# Hedgehog.net
KiCad netlist of a schematic drawn in Altium Designer
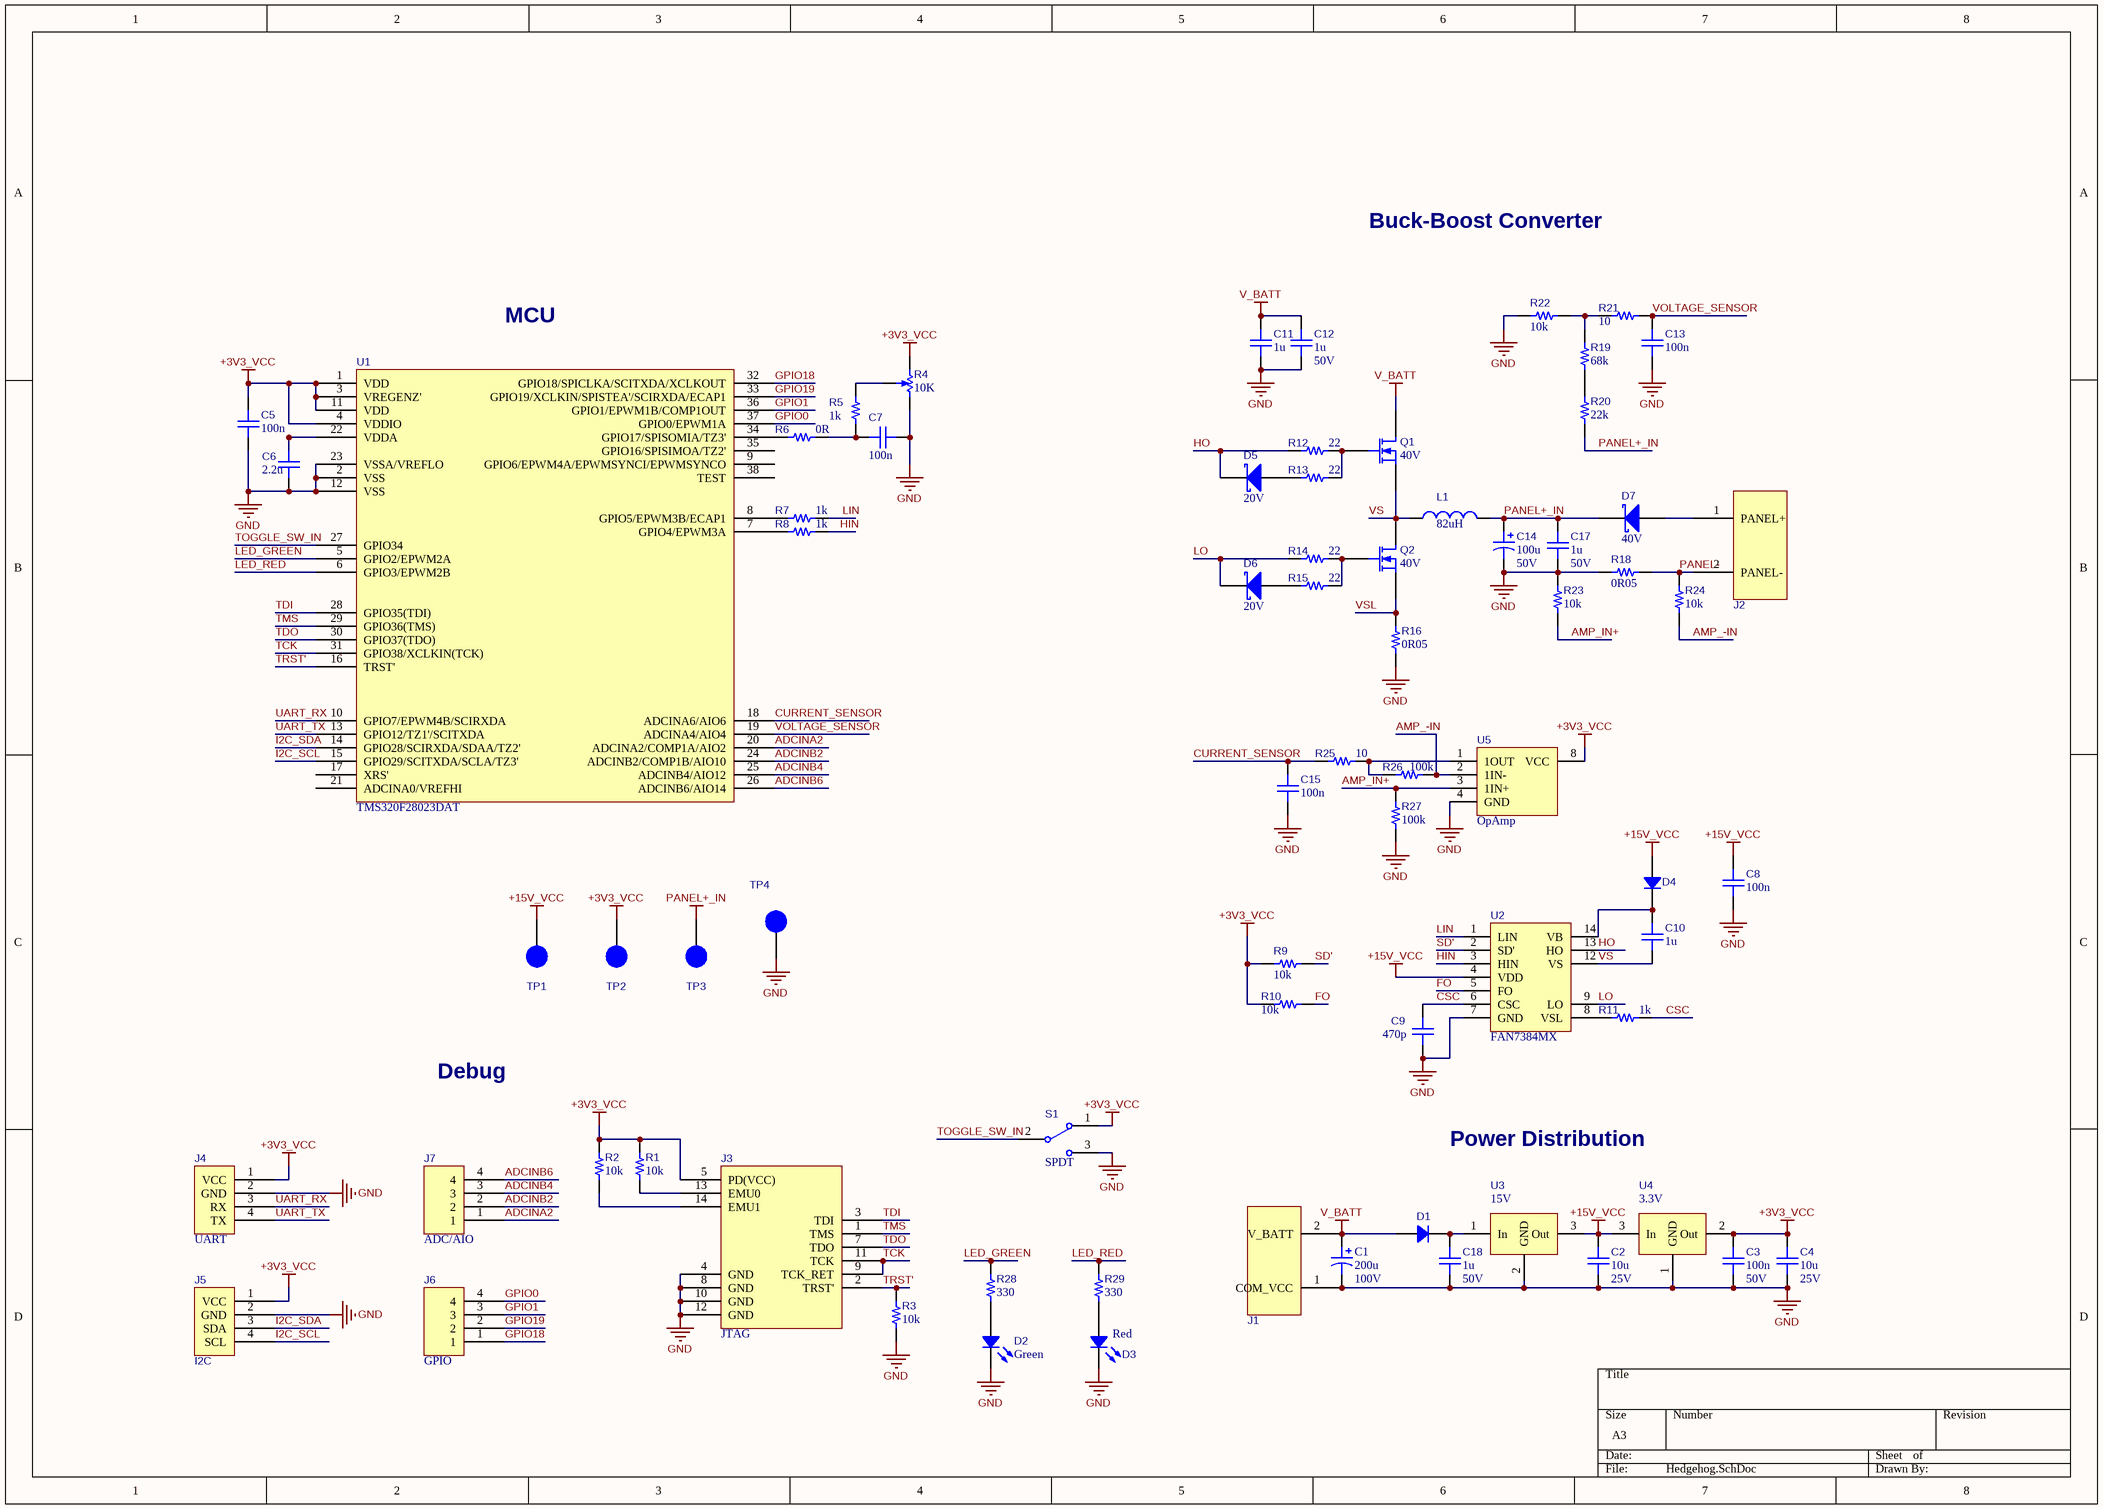
[diagram p0: Hedgehog.SchDoc]

(export (version "E")
  (design (tool "Eeschema 10.0.6"))
  (components
    (comp (ref "C1")
      (value "200u")
      (footprint "CAP-200uF-1000V-20%-THM-Radial")
      (description "Polarized Capacitor, 200uF, 100V Voltage Rating, Through Hole Radial Package")
      (fields (field (name "VOLTAGERATING") "100V"))
      (libsource (lib "hedgehog") (part "200u-100V-THM-Radial-20%"))
    )
    (comp (ref "C2")
      (value "10u")
      (footprint "CAP 1206/3216 Murata")
      (description "Capacitor, 10uF, 25V Voltage Rating, 1206 Package")
      (fields (field (name "VOLTAGERATING") "25V"))
      (libsource (lib "Capacitor SMD") (part "10u-25V-1206-10%"))
    )
    (comp (ref "C3")
      (value "100n")
      (footprint "CAP 0805/2012")
      (description "Capacitor, 100nF, 50V Voltage Rating, 0805 Package")
      (fields (field (name "VOLTAGERATING") "50V"))
      (libsource (lib "Capacitor SMD") (part "100n-50V-0805-10%"))
    )
    (comp (ref "C4")
      (value "10u")
      (footprint "CAP 1206/3216 Murata")
      (description "Capacitor, 10uF, 25V Voltage Rating, 1206 Package")
      (fields (field (name "VOLTAGERATING") "25V"))
      (libsource (lib "Capacitor SMD") (part "10u-25V-1206-10%"))
    )
    (comp (ref "C5")
      (value "100n")
      (footprint "CAP 0805/2012")
      (description "Capacitor, 100nF, 50V Voltage Rating, 0805 Package")
      (libsource (lib "Capacitor SMD") (part "100n-50V-0805-10%"))
    )
    (comp (ref "C6")
      (value "2.2u")
      (footprint "CAP 0805/2012")
      (description "Capacitor, 2.2uF, 25V Voltage Rating, 0805 Package")
      (libsource (lib "Capacitor SMD") (part "2.2u-25V-0805-10%"))
    )
    (comp (ref "C7")
      (value "100n")
      (footprint "CAP 0805/2012")
      (description "Capacitor, 100nF, 50V Voltage Rating, 0805 Package")
      (libsource (lib "Capacitor SMD") (part "100n-50V-0805-10%"))
    )
    (comp (ref "C8")
      (value "100n")
      (footprint "CAP 0805/2012")
      (description "Capacitor, 100nF, 50V Voltage Rating, 0805 Package")
      (libsource (lib "Capacitor SMD") (part "100n-50V-0805-10%"))
    )
    (comp (ref "C9")
      (value "470p")
      (footprint "CAP 0805/2012")
      (description "Capacitor, 470pF, 50V Voltage Rating, 0805 Package")
      (libsource (lib "Capacitor SMD") (part "470p-50V-0805-5%"))
    )
    (comp (ref "C10")
      (value "1u")
      (footprint "CAP 0805/2012")
      (description "Capacitor,1uF, 25V Voltage Rating, 0805 Package")
      (libsource (lib "Capacitor SMD") (part "1u-25V-0805-10%"))
    )
    (comp (ref "C11")
      (value "1u")
      (footprint "CAP-TH-Radial_1uF-Non_Polarised-KEMET")
      (description "Capacitor, 1uF, 63V Voltage Rating, RADIAL Package")
      (libsource (lib "PwrSupply-Schematics-Library") (part "1u-63V-THM-Radial-10%"))
    )
    (comp (ref "C12")
      (value "1u")
      (footprint "CAP 1206/3216 Murata")
      (description "Capacitor, 1uF, 50V Voltage Rating, 1206 Package")
      (fields (field (name "VOLTAGERATING") "50V"))
      (libsource (lib "Capacitor SMD") (part "1u-50V-1206-10%"))
    )
    (comp (ref "C13")
      (value "100n")
      (footprint "CAP 0805/2012")
      (description "Capacitor, 100nF, 50V Voltage Rating, 0805 Package")
      (libsource (lib "Capacitor SMD") (part "100n-50V-0805-10%"))
    )
    (comp (ref "C14")
      (value "100u")
      (footprint "CAP-100uF-50V-20%-THM-Radial Panasonic Electronic Components")
      (description "Polarized Capacitor, 100uF, 50V Voltage Rating, Through Hole Radial Package")
      (fields (field (name "VOLTAGERATING") "50V"))
      (libsource (lib "PwrSupply-Schematics-Library") (part "100u-50V-THM-Radial-20%"))
    )
    (comp (ref "C15")
      (value "100n")
      (footprint "CAP 0805/2012")
      (description "Capacitor, 100nF, 50V Voltage Rating, 0805 Package")
      (libsource (lib "Capacitor SMD") (part "100n-50V-0805-10%"))
    )
    (comp (ref "C17")
      (value "1u")
      (footprint "CAP 1206/3216 Murata")
      (description "Capacitor, 1uF, 50V Voltage Rating, 1206 Package")
      (fields (field (name "VOLTAGERATING") "50V"))
      (libsource (lib "Capacitor SMD") (part "1u-50V-1206-10%"))
    )
    (comp (ref "C18")
      (value "1u")
      (footprint "CAP 1206/3216 Murata")
      (description "Capacitor, 1uF, 50V Voltage Rating, 1206 Package")
      (fields (field (name "VOLTAGERATING") "50V"))
      (libsource (lib "Capacitor SMD") (part "1u-50V-1206-10%"))
    )
    (comp (ref "D1")
      (value "400V-1A-GenPurp-SMA")
      (footprint "SMA Diodes Incorporated")
      (description "Diode, 400V Voltage Rating, 1A Current Rating, General Purpose Type, SMA Package")
      (fields (field (name "MANUFACTURER") "ON Semiconductor"))
      (libsource (lib "Diode SMD") (part "400V-1A-GenPurp-SMA"))
    )
    (comp (ref "D2")
      (value "LED-Green-1206")
      (footprint "LED 1206/3216 Kingbright")
      (description "LED, Green Color, 1206 Package")
      (fields (field (name "MANUFACTURER") "Kingbright") (field (name "COLOR") "Green"))
      (libsource (lib "Diode SMD") (part "LED-Green-1206"))
    )
    (comp (ref "D3")
      (value "LED-Red-1206")
      (footprint "LED 1206/3216 Kingbright")
      (description "LED, Red Color, 1206 Package")
      (fields (field (name "MANUFACTURER") "Kingbright") (field (name "COLOR") "Red"))
      (libsource (lib "Diode SMD") (part "LED-Red-1206"))
    )
    (comp (ref "D4")
      (value "400V-2A-Fast-SMA")
      (footprint "SMA Diodes Incorporated")
      (description "Diode, 400V Voltage Rating, 2A Current Rating, Fast Type, SMA Package")
      (fields (field (name "MANUFACTURER") "ON Semiconductor"))
      (libsource (lib "Diode SMD") (part "400V-2A-Fast-SMA"))
    )
    (comp (ref "D5")
      (value "20V-1A-SCHOTTKY-SOD123W")
      (footprint "CFP3-SOD123W-Nexperia USA Inc.")
      (description "Diode, 20V Voltage Rating, 1A Current Rating, SCHOTTKY Type, SOD123W Package")
      (fields (field (name "MANUFACTURER") "Nexperia USA Inc.") (field (name "VOLTAGERATING") "20V"))
      (libsource (lib "PwrSupply-Schematics-Library") (part "20V-1A-SCHOTTKY-SOD123W"))
    )
    (comp (ref "D6")
      (value "20V-1A-SCHOTTKY-SOD123W")
      (footprint "CFP3-SOD123W-Nexperia USA Inc.")
      (description "Diode, 20V Voltage Rating, 1A Current Rating, SCHOTTKY Type, SOD123W Package")
      (fields (field (name "MANUFACTURER") "Nexperia USA Inc.") (field (name "VOLTAGERATING") "20V"))
      (libsource (lib "PwrSupply-Schematics-Library") (part "20V-1A-SCHOTTKY-SOD123W"))
    )
    (comp (ref "D7")
      (value "40V-5A-SCHOTTKY-SMC")
      (footprint "DIOM6959X25L")
      (description "Diode, 40V Voltage Rating, 5A Current Rating, SCHOTTKY Type, SMC Package")
      (fields (field (name "MANUFACTURER") "Diodes Incorporated") (field (name "VOLTAGERATING") "40V"))
      (libsource (lib "PwrSupply-Schematics-Library") (part "40V-5A-SCHOTTKY-SMC"))
    )
    (comp (ref "J1")
      (value "~")
      (footprint "TWO_PIN_CONNECTOR-15A-On Shore Technology Inc.")
      (description "Slide Toggle Switch, 300V Voltage Rating, 15A Current Rating,")
      (fields (field (name "MANUFACTURER") "On Shore Technology Inc."))
      (libsource (lib "") (part "TwoPin-Connector-15A-300V-THM_1"))
    )
    (comp (ref "J2")
      (value "~")
      (footprint "TWO_PIN_CONNECTOR-15A-On Shore Technology Inc.")
      (description "Slide Toggle Switch, 300V Voltage Rating, 15A Current Rating,")
      (fields (field (name "MANUFACTURER") "On Shore Technology Inc."))
      (libsource (lib "PwrSupply-Schematics-Library") (part "TwoPin-Connector-15A-300V-THM"))
    )
    (comp (ref "J3")
      (value "JTAG")
      (footprint "14Pin-Connector-2.54mmx2.54mmPitch On Shore Technology Inc.")
      (description "14Pin-Connector")
      (fields (field (name "MANUFACTURER") "On Shore Technology Inc."))
      (libsource (lib "PwrSupply-Schematics-Library") (part "14Pin-Connector"))
    )
    (comp (ref "J4")
      (value "UART")
      (footprint "4Pin_Connector-Wurth Electronics Inc.")
      (description "4Pin-Connector")
      (libsource (lib "PwrSupply-Schematics-Library") (part "4Pin-Connector"))
    )
    (comp (ref "J5")
      (value "I2C")
      (footprint "4Pin_Connector-Wurth Electronics Inc.")
      (description "4Pin-Connector")
      (libsource (lib "") (part "4Pin-Connector_2"))
    )
    (comp (ref "J6")
      (value "GPIO")
      (footprint "4Pin_Connector-Wurth Electronics Inc.")
      (description "4Pin-Connector")
      (libsource (lib "") (part "4Pin-Connector_1"))
    )
    (comp (ref "J7")
      (value "ADC/AIO")
      (footprint "4Pin_Connector-Wurth Electronics Inc.")
      (description "4Pin-Connector")
      (libsource (lib "") (part "4Pin-Connector_1"))
    )
    (comp (ref "L1")
      (value "82uH")
      (footprint "Inductor-82uH-Pulse Electronics Power")
      (description "82u, 6.5A Current Rating, 83mOhm Resistance, ThroughHole Package")
      (libsource (lib "PwrSupply-Schematics-Library") (part "82uH-6.5A-83mOhm"))
    )
    (comp (ref "Q1")
      (value "40V")
      (footprint "DPAK/TO252-3-5.46mmWidth(Tab) ON Semiconductor - VIAS")
      (description "N-CH, 40V Voltage Rating, 6A Current Rating,  1.71W Power Rating, DPAK Package")
      (libsource (lib "PwrSupply-Schematics-Library") (part "Mosfet-40V-6A-1.71W-SMD-DPAK"))
    )
    (comp (ref "Q2")
      (value "40V")
      (footprint "DPAK/TO252-3-5.46mmWidth(Tab) ON Semiconductor - VIAS")
      (description "N-CH, 40V Voltage Rating, 6A Current Rating,  1.71W Power Rating, DPAK Package")
      (libsource (lib "PwrSupply-Schematics-Library") (part "Mosfet-40V-6A-1.71W-SMD-DPAK"))
    )
    (comp (ref "R1")
      (value "10k")
      (footprint "RES 0805/2012")
      (description "Resistor, 10k, 125mW Power Rating, 0805 Package")
      (libsource (lib "Resistor SMD") (part "10k-125mW-0805-1%"))
    )
    (comp (ref "R2")
      (value "10k")
      (footprint "RES 0805/2012")
      (description "Resistor, 10k, 125mW Power Rating, 0805 Package")
      (libsource (lib "Resistor SMD") (part "10k-125mW-0805-1%"))
    )
    (comp (ref "R3")
      (value "10k")
      (footprint "RES 0805/2012")
      (description "Resistor, 10k, 125mW Power Rating, 0805 Package")
      (libsource (lib "Resistor SMD") (part "10k-125mW-0805-1%"))
    )
    (comp (ref "R4")
      (value "10K")
      (footprint "Potentiometer-TC33X-2-103E-Bourns Inc.")
      (description "Potentiometer, 10kOhm Resistance, Current Rating, 0.1W Power Rating")
      (fields (field (name "MANUFACTURER") "Bourns Inc."))
      (libsource (lib "PwrSupply-Schematics-Library") (part "Pot-10kOhm-0.1W-20%"))
    )
    (comp (ref "R5")
      (value "1k")
      (footprint "RES 0805/2012")
      (description "Resistor, 1k, 125mW Power Rating, 0805 Package")
      (libsource (lib "Resistor SMD") (part "1k-125mW-0805-1%"))
    )
    (comp (ref "R6")
      (value "0R")
      (footprint "RES 0805/2012")
      (description "Resistor, 0 , 125mW Power Rating, 0805 Package")
      (libsource (lib "Resistor SMD") (part "0k-125mW-0805-Jumper"))
    )
    (comp (ref "R7")
      (value "1k")
      (footprint "RES 0805/2012")
      (description "Resistor, 1k, 125mW Power Rating, 0805 Package")
      (libsource (lib "Resistor SMD") (part "1k-125mW-0805-1%"))
    )
    (comp (ref "R8")
      (value "1k")
      (footprint "RES 0805/2012")
      (description "Resistor, 1k, 125mW Power Rating, 0805 Package")
      (libsource (lib "Resistor SMD") (part "1k-125mW-0805-1%"))
    )
    (comp (ref "R9")
      (value "10k")
      (footprint "RES 0805/2012")
      (description "Resistor, 10k, 125mW Power Rating, 0805 Package")
      (libsource (lib "Resistor SMD") (part "10k-125mW-0805-1%"))
    )
    (comp (ref "R10")
      (value "10k")
      (footprint "RES 0805/2012")
      (description "Resistor, 10k, 125mW Power Rating, 0805 Package")
      (libsource (lib "Resistor SMD") (part "10k-125mW-0805-1%"))
    )
    (comp (ref "R11")
      (value "1k")
      (footprint "RES 0805/2012")
      (description "Resistor, 1k, 125mW Power Rating, 0805 Package")
      (libsource (lib "Resistor SMD") (part "1k-125mW-0805-1%"))
    )
    (comp (ref "R12")
      (value "22")
      (footprint "RES 0805/2012")
      (description "Resistor, 22, 125mW Power Rating, 0805 Package")
      (libsource (lib "Resistor SMD") (part "22-125mW-0805-1%"))
    )
    (comp (ref "R13")
      (value "22")
      (footprint "RES 0805/2012")
      (description "Resistor, 22, 125mW Power Rating, 0805 Package")
      (libsource (lib "Resistor SMD") (part "22-125mW-0805-1%"))
    )
    (comp (ref "R14")
      (value "22")
      (footprint "RES 0805/2012")
      (description "Resistor, 22, 125mW Power Rating, 0805 Package")
      (libsource (lib "Resistor SMD") (part "22-125mW-0805-1%"))
    )
    (comp (ref "R15")
      (value "22")
      (footprint "RES 0805/2012")
      (description "Resistor, 22, 125mW Power Rating, 0805 Package")
      (libsource (lib "Resistor SMD") (part "22-125mW-0805-1%"))
    )
    (comp (ref "R16")
      (value "0R05")
      (footprint "RES 2512/6432")
      (description "Resistor, 0.05 Ohm, 3W Power Rating, 2512 Package")
      (libsource (lib "PwrSupply-Schematics-Library") (part "RES-0.05-3W-SMD-2512-1%"))
    )
    (comp (ref "R18")
      (value "0R05")
      (footprint "RES 2512/6432")
      (description "Resistor, 0.05 Ohm, 3W Power Rating, 2512 Package")
      (libsource (lib "PwrSupply-Schematics-Library") (part "RES-0.05-3W-SMD-2512-1%"))
    )
    (comp (ref "R19")
      (value "68k")
      (footprint "RES 0805/2012")
      (description "Resistor, 68k, 125mW Power Rating, Package")
      (libsource (lib "Resistor SMD") (part "68k-125mW-0805-1%"))
    )
    (comp (ref "R20")
      (value "22k")
      (footprint "RES 0805/2012")
      (description "Resistor, 22k, 125mW Power Rating, 0805 Package")
      (libsource (lib "Resistor SMD") (part "22k-125mW-0805-1%"))
    )
    (comp (ref "R21")
      (value "10")
      (footprint "RES 0805/2012")
      (description "Resistor, 10, 125mW Power Rating, 0805 Package")
      (libsource (lib "Resistor SMD") (part "10-125mW-0805-1%"))
    )
    (comp (ref "R22")
      (value "10k")
      (footprint "RES 0805/2012")
      (description "Resistor, 10k, 125mW Power Rating, 0805 Package")
      (libsource (lib "Resistor SMD") (part "10k-125mW-0805-1%"))
    )
    (comp (ref "R23")
      (value "10k")
      (footprint "RES 0805/2012")
      (description "Resistor, 10k, 125mW Power Rating, 0805 Package")
      (libsource (lib "Resistor SMD") (part "10k-125mW-0805-1%"))
    )
    (comp (ref "R24")
      (value "10k")
      (footprint "RES 0805/2012")
      (description "Resistor, 10k, 125mW Power Rating, 0805 Package")
      (libsource (lib "Resistor SMD") (part "10k-125mW-0805-1%"))
    )
    (comp (ref "R25")
      (value "10")
      (footprint "RES 0805/2012")
      (description "Resistor, 10, 125mW Power Rating, 0805 Package")
      (libsource (lib "Resistor SMD") (part "10-125mW-0805-1%"))
    )
    (comp (ref "R26")
      (value "100k")
      (footprint "RES 0805/2012")
      (description "Resistor, 100k, 125mW Power Rating, 0805 Package")
      (libsource (lib "Resistor SMD") (part "100k-125mW-0805-1%"))
    )
    (comp (ref "R27")
      (value "100k")
      (footprint "RES 0805/2012")
      (description "Resistor, 100k, 125mW Power Rating, 0805 Package")
      (libsource (lib "Resistor SMD") (part "100k-125mW-0805-1%"))
    )
    (comp (ref "R28")
      (value "330")
      (footprint "RES 0805/2012")
      (description "Resistor, 330, 125mW Power Rating, 0805 Package")
      (libsource (lib "Resistor SMD") (part "330-125mW-0805-1%"))
    )
    (comp (ref "R29")
      (value "330")
      (footprint "RES 0805/2012")
      (description "Resistor, 330, 125mW Power Rating, 0805 Package")
      (libsource (lib "Resistor SMD") (part "330-125mW-0805-1%"))
    )
    (comp (ref "S1")
      (value "SPDT")
      (footprint "Toggle_Switch-SPDT-C&K")
      (description "Slide Toggle Switch, 12V Voltage Rating, 100mA Current Rating, Through Hole Package")
      (fields (field (name "MANUFACTURER") "C&K"))
      (libsource (lib "PwrSupply-Schematics-Library") (part "ToggleSwitch-SPDT-12V-100mA"))
    )
    (comp (ref "TP1")
      (value "TP_2mm_round")
      (footprint "TP_2mm_round")
      (libsource (lib "hedgehog") (part "TP_2mm_round"))
    )
    (comp (ref "TP2")
      (value "TP_2mm_round")
      (footprint "TP_2mm_round")
      (libsource (lib "hedgehog") (part "TP_2mm_round"))
    )
    (comp (ref "TP3")
      (value "TP_2mm_round")
      (footprint "TP_2mm_round")
      (libsource (lib "hedgehog") (part "TP_2mm_round"))
    )
    (comp (ref "TP4")
      (value "TP_2mm_round")
      (footprint "TP_2mm_round")
      (libsource (lib "hedgehog") (part "TP_2mm_round"))
    )
    (comp (ref "U1")
      (value "TMS320F28023DAT")
      (description "IC MCU 32BIT 64KB FLASH 38TSSOP")
      (fields (field (name "MANUFACTURER") "Texas Instruments"))
      (libsource (lib "PwrSupply-Schematics-Library") (part "MC-TMS320F28023DAT_Modified"))
    )
    (comp (ref "U2")
      (value "FAN7384MX")
      (footprint "14SOIC-3.9mmWidth ON Semiconductor")
      (description "Half-Bridge Gate Driver IC Non-Inverting 14-SOIC")
      (fields (field (name "MANUFACTURER") "ON Semiconductor"))
      (libsource (lib "IC Driver") (part "FAN7384MX"))
    )
    (comp (ref "U3")
      (value "15V")
      (footprint "DPAK/TO252-3-5.46mmWidth(Tab) ON Semiconductor")
      (description "Voltage Regulator, 15V OutputVoltage, 1A MaxCurrent, LDO Type, DPAK Package")
      (fields (field (name "MANUFACTURER") "ON Semiconductor") (field (name "OUTPUTVOLTAGE") "15V"))
      (libsource (lib "PwrSupply-Schematics-Library") (part "15V-1A-LDO-SMD-DPAK"))
    )
    (comp (ref "U4")
      (value "Voltage Regulator")
      (footprint "SOT223/TO261-4 Diodes Incorporated")
      (description "Voltage Regulator, 3.3V OutputVoltage, 1A MaxCurrent, LDO Type, SOT223 Package")
      (fields (field (name "MANUFACTURER") "Diodes Incorporated") (field (name "OUTPUTVOLTAGE") "3.3V"))
      (libsource (lib "IC Regulator") (part "3.3V-1A-LDO-SMD-SOT223_2"))
    )
    (comp (ref "U5")
      (value "OpAmp")
      (footprint "8SOIC-3.9mmWidth")
      (description "IC OPAMP GP 700KHZ 8SOIC")
      (fields (field (name "MANUFACTURER") "Texas Instruments"))
      (libsource (lib "IC OpAmp") (part "LM358AD"))
    )
  )
  (nets
    (net (code "1") (name "+3V3_VCC") (class "Default")
      (node (ref "C3") (pin "2") (pinfunction "2_2") (pintype "passive"))
      (node (ref "C4") (pin "1") (pinfunction "1_1") (pintype "passive"))
      (node (ref "C5") (pin "2") (pinfunction "2_2") (pintype "passive"))
      (node (ref "J3") (pin "5") (pinfunction "PD(VCC)_5") (pintype "passive"))
      (node (ref "J4") (pin "1") (pinfunction "VCC_1") (pintype "passive"))
      (node (ref "J5") (pin "1") (pinfunction "VCC_1") (pintype "passive"))
      (node (ref "R1") (pin "2") (pinfunction "2_2") (pintype "passive"))
      (node (ref "R10") (pin "1") (pinfunction "1_1") (pintype "passive"))
      (node (ref "R2") (pin "2") (pinfunction "2_2") (pintype "passive"))
      (node (ref "R4") (pin "3") (pinfunction "CW_3") (pintype "passive"))
      (node (ref "R9") (pin "1") (pinfunction "1_1") (pintype "passive"))
      (node (ref "S1") (pin "1") (pinfunction "3_1") (pintype "passive"))
      (node (ref "TP2") (pin "0") (pinfunction "0_0") (pintype "passive"))
      (node (ref "U1") (pin "1") (pinfunction "VDD_1") (pintype "passive"))
      (node (ref "U1") (pin "11") (pinfunction "VDD_11") (pintype "passive"))
      (node (ref "U1") (pin "3") (pinfunction "VREGENZ'_3") (pintype "passive"))
      (node (ref "U1") (pin "4") (pinfunction "VDDIO_4") (pintype "passive"))
      (node (ref "U4") (pin "2") (pinfunction "Out_2") (pintype "passive"))
      (node (ref "U5") (pin "8") (pinfunction "VCC_8") (pintype "passive"))
    )
    (net (code "2") (name "+15V_VCC") (class "Default")
      (node (ref "C2") (pin "1") (pinfunction "1_1") (pintype "passive"))
      (node (ref "C8") (pin "1") (pinfunction "1_1") (pintype "passive"))
      (node (ref "D4") (pin "1") (pinfunction "1_1") (pintype "passive"))
      (node (ref "TP1") (pin "0") (pinfunction "0_0") (pintype "passive"))
      (node (ref "U2") (pin "4") (pinfunction "VDD_4") (pintype "passive"))
      (node (ref "U3") (pin "3") (pinfunction "Out_3") (pintype "passive"))
      (node (ref "U4") (pin "3") (pinfunction "In_3") (pintype "passive"))
    )
    (net (code "3") (name "/ADCINA2") (class "Default")
      (node (ref "J7") (pin "1") (pinfunction "1_1") (pintype "passive"))
      (node (ref "U1") (pin "20") (pinfunction "ADCINA2/COMP1A/AIO2_20") (pintype "passive"))
    )
    (net (code "4") (name "/ADCINB2") (class "Default")
      (node (ref "J7") (pin "2") (pinfunction "2_2") (pintype "passive"))
      (node (ref "U1") (pin "24") (pinfunction "ADCINB2/COMP1B/AIO10_24") (pintype "passive"))
    )
    (net (code "5") (name "/ADCINB4") (class "Default")
      (node (ref "J7") (pin "3") (pinfunction "3_3") (pintype "passive"))
      (node (ref "U1") (pin "25") (pinfunction "ADCINB4/AIO12_25") (pintype "passive"))
    )
    (net (code "6") (name "/ADCINB6") (class "Default")
      (node (ref "J7") (pin "4") (pinfunction "4_4") (pintype "passive"))
      (node (ref "U1") (pin "26") (pinfunction "ADCINB6/AIO14_26") (pintype "passive"))
    )
    (net (code "7") (name "/AMP_-IN") (class "Default")
      (node (ref "R24") (pin "1") (pinfunction "1_1") (pintype "passive"))
      (node (ref "R26") (pin "2") (pinfunction "2_2") (pintype "passive"))
      (node (ref "U5") (pin "2") (pinfunction "1IN-_2") (pintype "passive"))
    )
    (net (code "8") (name "/AMP_IN+") (class "Default")
      (node (ref "R23") (pin "1") (pinfunction "1_1") (pintype "passive"))
      (node (ref "R27") (pin "1") (pinfunction "1_1") (pintype "passive"))
      (node (ref "U5") (pin "3") (pinfunction "1IN+_3") (pintype "passive"))
    )
    (net (code "9") (name "/CSC") (class "Default")
      (node (ref "C9") (pin "2") (pinfunction "2_2") (pintype "passive"))
      (node (ref "R11") (pin "1") (pinfunction "1_1") (pintype "passive"))
      (node (ref "U2") (pin "6") (pinfunction "CSC_6") (pintype "passive"))
    )
    (net (code "10") (name "/CURRENT_SENSOR") (class "Default")
      (node (ref "C15") (pin "1") (pinfunction "1_1") (pintype "passive"))
      (node (ref "R25") (pin "2") (pinfunction "2_2") (pintype "passive"))
      (node (ref "U1") (pin "18") (pinfunction "ADCINA6/AIO6_18") (pintype "passive"))
    )
    (net (code "11") (name "/FO") (class "Default")
      (node (ref "R10") (pin "2") (pinfunction "2_2") (pintype "passive"))
      (node (ref "U2") (pin "5") (pinfunction "FO_5") (pintype "passive"))
    )
    (net (code "12") (name "/GPIO0") (class "Default")
      (node (ref "J6") (pin "4") (pinfunction "4_4") (pintype "passive"))
      (node (ref "U1") (pin "37") (pinfunction "GPIO0/EPWM1A_37") (pintype "passive"))
    )
    (net (code "13") (name "/GPIO1") (class "Default")
      (node (ref "J6") (pin "3") (pinfunction "3_3") (pintype "passive"))
      (node (ref "U1") (pin "36") (pinfunction "GPIO1/EPWM1B/COMP1OUT_36") (pintype "passive"))
    )
    (net (code "14") (name "/GPIO18") (class "Default")
      (node (ref "J6") (pin "1") (pinfunction "1_1") (pintype "passive"))
      (node (ref "U1") (pin "32") (pinfunction "GPIO18/SPICLKA/SCITXDA/XCLKOUT_32") (pintype "passive"))
    )
    (net (code "15") (name "/GPIO19") (class "Default")
      (node (ref "J6") (pin "2") (pinfunction "2_2") (pintype "passive"))
      (node (ref "U1") (pin "33") (pinfunction "GPIO19/XCLKIN/SPISTEA'/SCIRXDA/ECAP1_33") (pintype "passive"))
    )
    (net (code "16") (name "/HIN") (class "Default")
      (node (ref "R8") (pin "2") (pinfunction "2_2") (pintype "passive"))
      (node (ref "U2") (pin "3") (pinfunction "HIN_3") (pintype "passive"))
    )
    (net (code "17") (name "/HO") (class "Default")
      (node (ref "D5") (pin "2") (pinfunction "K_2") (pintype "passive"))
      (node (ref "R12") (pin "1") (pinfunction "1_1") (pintype "passive"))
      (node (ref "U2") (pin "13") (pinfunction "HO_13") (pintype "passive"))
    )
    (net (code "18") (name "/I2C_SCL") (class "Default")
      (node (ref "J5") (pin "4") (pinfunction "SCL_4") (pintype "passive"))
      (node (ref "U1") (pin "15") (pinfunction "GPIO29/SCITXDA/SCLA/TZ3'_15") (pintype "passive"))
    )
    (net (code "19") (name "/I2C_SDA") (class "Default")
      (node (ref "J5") (pin "3") (pinfunction "SDA_3") (pintype "passive"))
      (node (ref "U1") (pin "14") (pinfunction "GPIO28/SCIRXDA/SDAA/TZ2'_14") (pintype "passive"))
    )
    (net (code "20") (name "/LED_GREEN") (class "Default")
      (node (ref "R28") (pin "2") (pinfunction "2_2") (pintype "passive"))
      (node (ref "U1") (pin "5") (pinfunction "GPIO2/EPWM2A_5") (pintype "passive"))
    )
    (net (code "21") (name "/LED_RED") (class "Default")
      (node (ref "R29") (pin "2") (pinfunction "2_2") (pintype "passive"))
      (node (ref "U1") (pin "6") (pinfunction "GPIO3/EPWM2B_6") (pintype "passive"))
    )
    (net (code "22") (name "/LIN") (class "Default")
      (node (ref "R7") (pin "2") (pinfunction "2_2") (pintype "passive"))
      (node (ref "U2") (pin "1") (pinfunction "LIN_1") (pintype "passive"))
    )
    (net (code "23") (name "/LO") (class "Default")
      (node (ref "D6") (pin "2") (pinfunction "K_2") (pintype "passive"))
      (node (ref "R14") (pin "1") (pinfunction "1_1") (pintype "passive"))
      (node (ref "U2") (pin "9") (pinfunction "LO_9") (pintype "passive"))
    )
    (net (code "24") (name "/PANEL-") (class "Default")
      (node (ref "J2") (pin "2") (pinfunction "PANEL-_2") (pintype "passive"))
      (node (ref "R18") (pin "2") (pinfunction "2_2") (pintype "passive"))
      (node (ref "R24") (pin "2") (pinfunction "2_2") (pintype "passive"))
    )
    (net (code "25") (name "/SD'") (class "Default")
      (node (ref "R9") (pin "2") (pinfunction "2_2") (pintype "passive"))
      (node (ref "U2") (pin "2") (pinfunction "SD'_2") (pintype "passive"))
    )
    (net (code "26") (name "/TCK") (class "Default")
      (node (ref "J3") (pin "11") (pinfunction "TCK_11") (pintype "passive"))
      (node (ref "J3") (pin "9") (pinfunction "TCK_RET_9") (pintype "passive"))
      (node (ref "U1") (pin "31") (pinfunction "GPIO38/XCLKIN(TCK)_31") (pintype "passive"))
    )
    (net (code "27") (name "/TDI") (class "Default")
      (node (ref "J3") (pin "3") (pinfunction "TDI_3") (pintype "passive"))
      (node (ref "U1") (pin "28") (pinfunction "GPIO35(TDI)_28") (pintype "passive"))
    )
    (net (code "28") (name "/TDO") (class "Default")
      (node (ref "J3") (pin "7") (pinfunction "TDO_7") (pintype "passive"))
      (node (ref "U1") (pin "30") (pinfunction "GPIO37(TDO)_30") (pintype "passive"))
    )
    (net (code "29") (name "/TMS") (class "Default")
      (node (ref "J3") (pin "1") (pinfunction "TMS_1") (pintype "passive"))
      (node (ref "U1") (pin "29") (pinfunction "GPIO36(TMS)_29") (pintype "passive"))
    )
    (net (code "30") (name "/TOGGLE_SW_IN") (class "Default")
      (node (ref "S1") (pin "2") (pinfunction "2_2") (pintype "passive"))
      (node (ref "U1") (pin "27") (pinfunction "GPIO34_27") (pintype "passive"))
    )
    (net (code "31") (name "/TRST'") (class "Default")
      (node (ref "J3") (pin "2") (pinfunction "TRST'_2") (pintype "passive"))
      (node (ref "R3") (pin "2") (pinfunction "2_2") (pintype "passive"))
      (node (ref "U1") (pin "16") (pinfunction "TRST'_16") (pintype "passive"))
    )
    (net (code "32") (name "/UART_RX") (class "Default")
      (node (ref "J4") (pin "3") (pinfunction "RX_3") (pintype "passive"))
      (node (ref "U1") (pin "10") (pinfunction "GPIO7/EPWM4B/SCIRXDA_10") (pintype "passive"))
    )
    (net (code "33") (name "/UART_TX") (class "Default")
      (node (ref "J4") (pin "4") (pinfunction "TX_4") (pintype "passive"))
      (node (ref "U1") (pin "13") (pinfunction "GPIO12/TZ1'/SCITXDA_13") (pintype "passive"))
    )
    (net (code "34") (name "/VOLTAGE_SENSOR") (class "Default")
      (node (ref "C13") (pin "2") (pinfunction "2_2") (pintype "passive"))
      (node (ref "R21") (pin "2") (pinfunction "2_2") (pintype "passive"))
      (node (ref "U1") (pin "19") (pinfunction "ADCINA4/AIO4_19") (pintype "passive"))
    )
    (net (code "35") (name "/VS") (class "Default")
      (node (ref "C10") (pin "1") (pinfunction "1_1") (pintype "passive"))
      (node (ref "L1") (pin "1") (pinfunction "1_1") (pintype "passive"))
      (node (ref "Q1") (pin "3") (pinfunction "S_3") (pintype "passive"))
      (node (ref "Q2") (pin "2") (pinfunction "D_2") (pintype "passive"))
      (node (ref "U2") (pin "12") (pinfunction "VS_12") (pintype "passive"))
    )
    (net (code "36") (name "/VSL") (class "Default")
      (node (ref "Q2") (pin "3") (pinfunction "S_3") (pintype "passive"))
      (node (ref "R16") (pin "2") (pinfunction "2_2") (pintype "passive"))
    )
    (net (code "37") (name "GND") (class "Default")
      (node (ref "C1") (pin "2") (pinfunction "2_2") (pintype "passive"))
      (node (ref "C11") (pin "1") (pinfunction "1_1") (pintype "passive"))
      (node (ref "C12") (pin "1") (pinfunction "1_1") (pintype "passive"))
      (node (ref "C13") (pin "1") (pinfunction "1_1") (pintype "passive"))
      (node (ref "C14") (pin "2") (pinfunction "2_2") (pintype "passive"))
      (node (ref "C15") (pin "2") (pinfunction "2_2") (pintype "passive"))
      (node (ref "C17") (pin "1") (pinfunction "1_1") (pintype "passive"))
      (node (ref "C18") (pin "1") (pinfunction "1_1") (pintype "passive"))
      (node (ref "C2") (pin "2") (pinfunction "2_2") (pintype "passive"))
      (node (ref "C3") (pin "1") (pinfunction "1_1") (pintype "passive"))
      (node (ref "C4") (pin "2") (pinfunction "2_2") (pintype "passive"))
      (node (ref "C5") (pin "1") (pinfunction "1_1") (pintype "passive"))
      (node (ref "C6") (pin "1") (pinfunction "1_1") (pintype "passive"))
      (node (ref "C7") (pin "1") (pinfunction "1_1") (pintype "passive"))
      (node (ref "C8") (pin "2") (pinfunction "2_2") (pintype "passive"))
      (node (ref "C9") (pin "1") (pinfunction "1_1") (pintype "passive"))
      (node (ref "D2") (pin "2") (pinfunction "2_2") (pintype "passive"))
      (node (ref "D3") (pin "2") (pinfunction "2_2") (pintype "passive"))
      (node (ref "J1") (pin "1") (pinfunction "COM_VCC_1") (pintype "passive"))
      (node (ref "J3") (pin "10") (pinfunction "GND_10") (pintype "passive"))
      (node (ref "J3") (pin "12") (pinfunction "GND_12") (pintype "passive"))
      (node (ref "J3") (pin "4") (pinfunction "GND_4") (pintype "passive"))
      (node (ref "J3") (pin "8") (pinfunction "GND_8") (pintype "passive"))
      (node (ref "J4") (pin "2") (pinfunction "GND_2") (pintype "passive"))
      (node (ref "J5") (pin "2") (pinfunction "GND_2") (pintype "passive"))
      (node (ref "R16") (pin "1") (pinfunction "1_1") (pintype "passive"))
      (node (ref "R18") (pin "1") (pinfunction "1_1") (pintype "passive"))
      (node (ref "R22") (pin "2") (pinfunction "2_2") (pintype "passive"))
      (node (ref "R23") (pin "2") (pinfunction "2_2") (pintype "passive"))
      (node (ref "R27") (pin "2") (pinfunction "2_2") (pintype "passive"))
      (node (ref "R3") (pin "1") (pinfunction "1_1") (pintype "passive"))
      (node (ref "R4") (pin "1") (pinfunction "CCW_1") (pintype "passive"))
      (node (ref "S1") (pin "3") (pinfunction "1_3") (pintype "passive"))
      (node (ref "TP4") (pin "0") (pinfunction "0_0") (pintype "passive"))
      (node (ref "U1") (pin "12") (pinfunction "VSS_12") (pintype "passive"))
      (node (ref "U1") (pin "2") (pinfunction "VSS_2") (pintype "passive"))
      (node (ref "U1") (pin "23") (pinfunction "VSSA/VREFLO_23") (pintype "passive"))
      (node (ref "U2") (pin "7") (pinfunction "GND_7") (pintype "passive"))
      (node (ref "U3") (pin "2") (pinfunction "GND_2") (pintype "passive"))
      (node (ref "U4") (pin "1") (pinfunction "GND_1") (pintype "passive"))
      (node (ref "U5") (pin "4") (pinfunction "GND_4") (pintype "passive"))
    )
    (net (code "38") (name "Net-(C7-Pad2)") (class "Default")
      (node (ref "C7") (pin "2") (pinfunction "2_2") (pintype "passive"))
      (node (ref "R5") (pin "1") (pinfunction "1_1") (pintype "passive"))
      (node (ref "R6") (pin "2") (pinfunction "2_2") (pintype "passive"))
    )
    (net (code "39") (name "Net-(D2-Pad1)") (class "Default")
      (node (ref "D2") (pin "1") (pinfunction "1_1") (pintype "passive"))
      (node (ref "R28") (pin "1") (pinfunction "1_1") (pintype "passive"))
    )
    (net (code "40") (name "Net-(D3-Pad1)") (class "Default")
      (node (ref "D3") (pin "1") (pinfunction "1_1") (pintype "passive"))
      (node (ref "R29") (pin "1") (pinfunction "1_1") (pintype "passive"))
    )
    (net (code "41") (name "Net-(D5-A)") (class "Default")
      (node (ref "D5") (pin "1") (pinfunction "A_1") (pintype "passive"))
      (node (ref "R13") (pin "1") (pinfunction "1_1") (pintype "passive"))
    )
    (net (code "42") (name "Net-(D6-A)") (class "Default")
      (node (ref "D6") (pin "1") (pinfunction "A_1") (pintype "passive"))
      (node (ref "R15") (pin "1") (pinfunction "1_1") (pintype "passive"))
    )
    (net (code "43") (name "Net-(D7-A)") (class "Default")
      (node (ref "D7") (pin "1") (pinfunction "A_1") (pintype "passive"))
      (node (ref "J2") (pin "1") (pinfunction "PANEL+_1") (pintype "passive"))
    )
    (net (code "44") (name "Net-(J3-EMU0)") (class "Default")
      (node (ref "J3") (pin "13") (pinfunction "EMU0_13") (pintype "passive"))
      (node (ref "R1") (pin "1") (pinfunction "1_1") (pintype "passive"))
    )
    (net (code "45") (name "Net-(J3-EMU1)") (class "Default")
      (node (ref "J3") (pin "14") (pinfunction "EMU1_14") (pintype "passive"))
      (node (ref "R2") (pin "1") (pinfunction "1_1") (pintype "passive"))
    )
    (net (code "46") (name "Net-(Q1-G)") (class "Default")
      (node (ref "Q1") (pin "1") (pinfunction "G_1") (pintype "passive"))
      (node (ref "R12") (pin "2") (pinfunction "2_2") (pintype "passive"))
      (node (ref "R13") (pin "2") (pinfunction "2_2") (pintype "passive"))
    )
    (net (code "47") (name "Net-(Q2-G)") (class "Default")
      (node (ref "Q2") (pin "1") (pinfunction "G_1") (pintype "passive"))
      (node (ref "R14") (pin "2") (pinfunction "2_2") (pintype "passive"))
      (node (ref "R15") (pin "2") (pinfunction "2_2") (pintype "passive"))
    )
    (net (code "48") (name "Net-(R4-W)") (class "Default")
      (node (ref "R4") (pin "2") (pinfunction "W_2") (pintype "passive"))
      (node (ref "R5") (pin "2") (pinfunction "2_2") (pintype "passive"))
    )
    (net (code "49") (name "Net-(R19-Pad1)") (class "Default")
      (node (ref "R19") (pin "1") (pinfunction "1_1") (pintype "passive"))
      (node (ref "R20") (pin "2") (pinfunction "2_2") (pintype "passive"))
    )
    (net (code "50") (name "Net-(R19-Pad2)") (class "Default")
      (node (ref "R19") (pin "2") (pinfunction "2_2") (pintype "passive"))
      (node (ref "R21") (pin "1") (pinfunction "1_1") (pintype "passive"))
      (node (ref "R22") (pin "1") (pinfunction "1_1") (pintype "passive"))
    )
    (net (code "51") (name "Net-(U1-GPIO4{slash}EPWM3A)") (class "Default")
      (node (ref "R8") (pin "1") (pinfunction "1_1") (pintype "passive"))
      (node (ref "U1") (pin "7") (pinfunction "GPIO4/EPWM3A_7") (pintype "passive"))
    )
    (net (code "52") (name "Net-(U1-GPIO5{slash}EPWM3B{slash}ECAP1)") (class "Default")
      (node (ref "R7") (pin "1") (pinfunction "1_1") (pintype "passive"))
      (node (ref "U1") (pin "8") (pinfunction "GPIO5/EPWM3B/ECAP1_8") (pintype "passive"))
    )
    (net (code "53") (name "Net-(U1-GPIO17{slash}SPISOMIA{slash}TZ3')") (class "Default")
      (node (ref "R6") (pin "1") (pinfunction "1_1") (pintype "passive"))
      (node (ref "U1") (pin "34") (pinfunction "GPIO17/SPISOMIA/TZ3'_34") (pintype "passive"))
    )
    (net (code "54") (name "Net-(U1-VDDA)") (class "Default")
      (node (ref "C6") (pin "2") (pinfunction "2_2") (pintype "passive"))
      (node (ref "U1") (pin "22") (pinfunction "VDDA_22") (pintype "passive"))
    )
    (net (code "55") (name "Net-(U2-VB)") (class "Default")
      (node (ref "C10") (pin "2") (pinfunction "2_2") (pintype "passive"))
      (node (ref "D4") (pin "2") (pinfunction "2_2") (pintype "passive"))
      (node (ref "U2") (pin "14") (pinfunction "VB_14") (pintype "passive"))
    )
    (net (code "56") (name "Net-(U2-VSL)") (class "Default")
      (node (ref "R11") (pin "2") (pinfunction "2_2") (pintype "passive"))
      (node (ref "U2") (pin "8") (pinfunction "VSL_8") (pintype "passive"))
    )
    (net (code "57") (name "Net-(U3-In)") (class "Default")
      (node (ref "C18") (pin "2") (pinfunction "2_2") (pintype "passive"))
      (node (ref "D1") (pin "2") (pinfunction "2_2") (pintype "passive"))
      (node (ref "U3") (pin "1") (pinfunction "In_1") (pintype "passive"))
    )
    (net (code "58") (name "Net-(U5-1OUT)") (class "Default")
      (node (ref "R25") (pin "1") (pinfunction "1_1") (pintype "passive"))
      (node (ref "R26") (pin "1") (pinfunction "1_1") (pintype "passive"))
      (node (ref "U5") (pin "1") (pinfunction "1OUT_1") (pintype "passive"))
    )
    (net (code "59") (name "PANEL+_IN") (class "Default")
      (node (ref "C14") (pin "1") (pinfunction "1_1") (pintype "passive"))
      (node (ref "C17") (pin "2") (pinfunction "2_2") (pintype "passive"))
      (node (ref "D7") (pin "2") (pinfunction "K_2") (pintype "passive"))
      (node (ref "L1") (pin "2") (pinfunction "2_2") (pintype "passive"))
      (node (ref "R20") (pin "1") (pinfunction "1_1") (pintype "passive"))
      (node (ref "TP3") (pin "0") (pinfunction "0_0") (pintype "passive"))
    )
    (net (code "60") (name "V_BATT") (class "Default")
      (node (ref "C1") (pin "1") (pinfunction "1_1") (pintype "passive"))
      (node (ref "C11") (pin "2") (pinfunction "2_2") (pintype "passive"))
      (node (ref "C12") (pin "2") (pinfunction "2_2") (pintype "passive"))
      (node (ref "D1") (pin "1") (pinfunction "1_1") (pintype "passive"))
      (node (ref "J1") (pin "2") (pinfunction "V_BATT_2") (pintype "passive"))
      (node (ref "Q1") (pin "2") (pinfunction "D_2") (pintype "passive"))
    )
    (net (code "61") (name "unconnected-(J3-N{slash}C-Pad6)") (class "Default")
      (node (ref "J3") (pin "6") (pinfunction "N/C_6") (pintype "passive"))
    )
    (net (code "62") (name "unconnected-(U1-ADCINA0{slash}VREFHI-Pad21)") (class "Default")
      (node (ref "U1") (pin "21") (pinfunction "ADCINA0/VREFHI_21") (pintype "passive"))
    )
    (net (code "63") (name "unconnected-(U1-GPIO6{slash}EPWM4A{slash}EPWMSYNCI{slash}EPWMSYNCO-Pad9)") (class "Default")
      (node (ref "U1") (pin "9") (pinfunction "GPIO6/EPWM4A/EPWMSYNCI/EPWMSYNCO_9") (pintype "passive"))
    )
    (net (code "64") (name "unconnected-(U1-GPIO16{slash}SPISIMOA{slash}TZ2'-Pad35)") (class "Default")
      (node (ref "U1") (pin "35") (pinfunction "GPIO16/SPISIMOA/TZ2'_35") (pintype "passive"))
    )
    (net (code "65") (name "unconnected-(U1-TEST-Pad38)") (class "Default")
      (node (ref "U1") (pin "38") (pinfunction "TEST_38") (pintype "passive"))
    )
    (net (code "66") (name "unconnected-(U1-XRS'-Pad17)") (class "Default")
      (node (ref "U1") (pin "17") (pinfunction "XRS'_17") (pintype "passive"))
    )
    (net (code "67") (name "unconnected-(U2-NC-Pad10)") (class "Default")
      (node (ref "U2") (pin "10") (pinfunction "NC_10") (pintype "passive"))
    )
    (net (code "68") (name "unconnected-(U2-NC-Pad11)") (class "Default")
      (node (ref "U2") (pin "11") (pinfunction "NC_11") (pintype "passive"))
    )
    (net (code "69") (name "unconnected-(U5-2IN+-Pad5)") (class "Default")
      (node (ref "U5") (pin "5") (pinfunction "2IN+_5") (pintype "passive"))
    )
    (net (code "70") (name "unconnected-(U5-2IN--Pad6)") (class "Default")
      (node (ref "U5") (pin "6") (pinfunction "2IN-_6") (pintype "passive"))
    )
    (net (code "71") (name "unconnected-(U5-2OUT-Pad7)") (class "Default")
      (node (ref "U5") (pin "7") (pinfunction "2OUT_7") (pintype "passive"))
    )
  )
)
